# CAN_Bus.net
KiCad netlist of a schematic drawn in Altium Designer
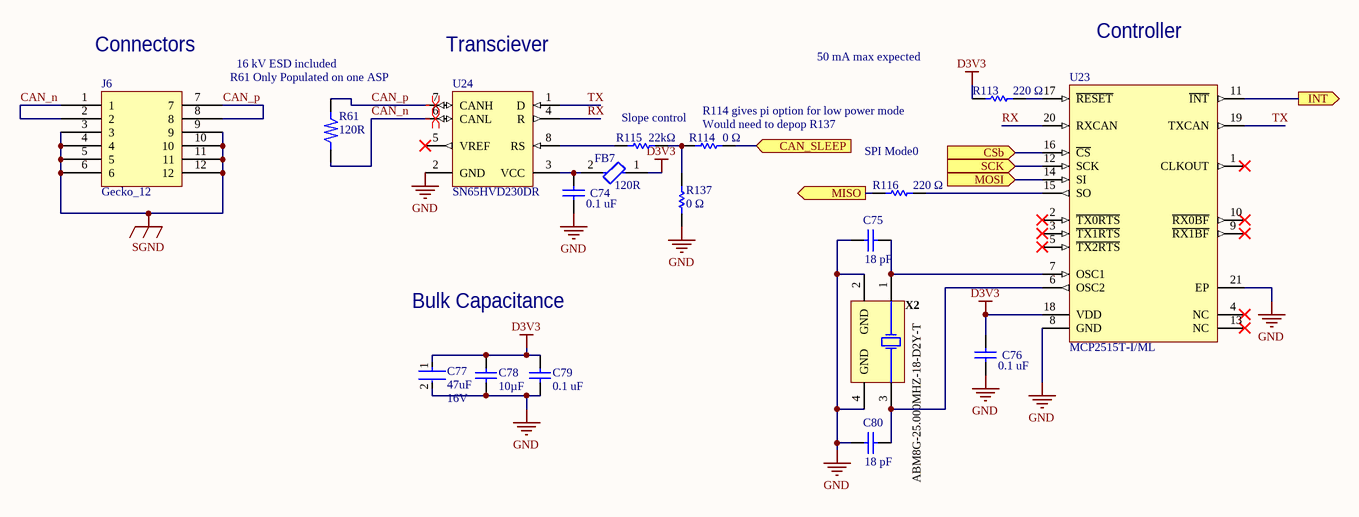
[diagram p0: CAN_Bus.SchDoc]

(export (version "E")
  (design (tool "Eeschema 10.0.6"))
  (components
    (comp (ref "C74")
      (value "0.1 uF")
      (footprint "CAPC0402(1005)60_L")
      (description "CAP 100nF 16V ±5% 0402 (1005 Metric) Thickness 0.6mm SMD")
      (fields (field (name "TOLERANCE") "Â±5%"))
      (libsource (lib "Altium Content Vault") (part "CAP"))
    )
    (comp (ref "C75")
      (value "GRM1555C1H180JA01D")
      (footprint "CAPC1005X55X25LL05T10")
      (fields (field (name "MANUFACTURER") "Murata") (field (name "CAPACITANCE") "18 pF"))
      (libsource (lib "Altium Content Vault") (part "CAP"))
    )
    (comp (ref "C76")
      (value "0.1 uF")
      (footprint "CAPC0402(1005)60_L")
      (description "CAP 100nF 16V ±5% 0402 (1005 Metric) Thickness 0.6mm SMD")
      (fields (field (name "TOLERANCE") "Â±5%"))
      (libsource (lib "Altium Content Vault") (part "CAP"))
    )
    (comp (ref "C77")
      (value "GRT32EC81C476ME13L")
      (footprint "FP-GRT32E-0_3-IPC_C")
      (description "Multi-Layer Ceramic Capacitor 47uF 16V X6S ±20% 1210 Emboss T/R")
      (fields
        (field (name "CAPACITANCE") "47uF")
        (field (name "VOLTAGE RATING") "16V")
        (field (name "TOLERANCE") "20%")
      )
      (libsource (lib "Altium Content Vault") (part "02cd4be3c70576c341d710602a673aa"))
    )
    (comp (ref "C78")
      (value "EMK107BBJ106MA-T")
      (footprint "CAPC1608X100X35LL20T25")
      (description "Chip Capacitor, 10 uF, +/- 20%, 16 V, -55 to 85 degC, 0603 (1608 Metric), RoHS, Tape and Reel")
      (fields
        (field (name "CAPACITANCE") "10µF")
        (field (name "MANUFACTURER") "Taiyo Yuden")
        (field (name "TOLERANCE") "±20%")
      )
      (libsource (lib "Altium Content Vault") (part "CAP-NP-2"))
    )
    (comp (ref "C79")
      (value "0.1 uF")
      (footprint "CAPC0402(1005)60_L")
      (description "CAP 100nF 16V ±5% 0402 (1005 Metric) Thickness 0.6mm SMD")
      (fields (field (name "TOLERANCE") "Â±5%"))
      (libsource (lib "Altium Content Vault") (part "CAP"))
    )
    (comp (ref "C80")
      (value "GRM1555C1H180JA01D")
      (footprint "CAPC1005X55X25LL05T10")
      (fields (field (name "MANUFACTURER") "Murata") (field (name "CAPACITANCE") "18 pF"))
      (libsource (lib "Altium Content Vault") (part "CAP"))
    )
    (comp (ref "FB7")
      (value "BLM18PG121SH1D")
      (footprint "FP-BLM18-0_15-t0_8-IPC_C")
      (description "Chip Ferrite Bead, 0603, 120Ω @ 100MHz, 0.05Ω, 25%, 2A")
      (fields (field (name "IMPEDANCE") "120R") (field (name "TOLERANCE") "25%"))
      (libsource (lib "Altium Content Vault") (part "5f30dd21d616792df468990f7003faa"))
    )
    (comp (ref "J6") (value "Gecko_12") (footprint "GECK12") (libsource (lib "Hrafn") (part "Gecko_12")))
    (comp (ref "R61")
      (value "R")
      (footprint "RESC1608X08L")
      (description "ROHM - ESR03EZPJ121 - RES, AEC-Q200, THICK FILM, 120R, 5%, 0603 ROHS COMPLIANT: YES")
      (fields (field (name "TOLERANCE") "5%") (field (name "RESISTANCE") "120R"))
      (libsource (lib "Hrafn") (part "R"))
    )
    (comp (ref "R113")
      (value "220 Ω")
      (footprint "RESC1005X40X25LL05T05")
      (fields (field (name "PART NUMBER") "CRCW040220K0FKED") (field (name "MANUFACTURER") "Vishay Dale"))
      (libsource (lib "Altium Content Vault") (part "RES"))
    )
    (comp (ref "R114")
      (value "ERJ2GE0R00X")
      (footprint "RESC1005X40X25LL05T05")
      (description "Chip Resistor, 0 Ohm, 0.1 W, -55 to 155 degC, 0402 (1005 Metric), RoHS, Tape and Reel")
      (fields
        (field (name "MANUFACTURER") "Panasonic")
        (field (name "RESISTANCE") "0 Ω")
        (field (name "TOLERANCE") "5%")
      )
      (libsource (lib "Altium Content Vault") (part "RES-2"))
    )
    (comp (ref "R115")
      (value "22kΩ")
      (footprint "RESC1005X40X25LL05T05")
      (fields (field (name "MANUFACTURER") "Panasonic") (field (name "PART NUMBER") "ERJ-2GEJ223X"))
      (libsource (lib "Altium Content Vault") (part "RES"))
    )
    (comp (ref "R116")
      (value "220 Ω")
      (footprint "RESC1005X40X25LL05T05")
      (fields (field (name "PART NUMBER") "CRCW040220K0FKED") (field (name "MANUFACTURER") "Vishay Dale"))
      (libsource (lib "Altium Content Vault") (part "RES"))
    )
    (comp (ref "R137")
      (value "ERJ2GE0R00X")
      (footprint "RESC1005X40X25LL05T05")
      (description "Chip Resistor, 0 Ohm, 0.1 W, -55 to 155 degC, 0402 (1005 Metric), RoHS, Tape and Reel")
      (fields
        (field (name "MANUFACTURER") "Panasonic")
        (field (name "RESISTANCE") "0 Ω")
        (field (name "TOLERANCE") "5%")
      )
      (libsource (lib "Altium Content Vault") (part "RES-2"))
    )
    (comp (ref "U23")
      (value "MCP2515T-I/ML")
      (footprint "QFN-ML20_N")
      (description "Stand-Alone CAN Controller With SPI Interface, 20-Pin QFN, Industrial Temperature, Tape and Reel")
      (libsource (lib "Altium Content Vault") (part "COM-CAN-MCP2515-21"))
    )
    (comp (ref "U24")
      (value "SN65HVD230DR")
      (footprint "D0008A_L")
      (fields (field (name "MANUFACTURER") "Texas Instruments"))
      (libsource (lib "Altium Content Vault") (part "TI-SN65HVD230-SOIC_D-8"))
    )
    (comp (ref "X2")
      (value "ABM8G-25.000MHZ-18-D2Y-T")
      (footprint "ABRA-ABM8G_V")
      (fields (field (name "MANUFACTURER") "ABRACON") (field (name "TOLERANCE") "20PPM"))
      (libsource (lib "Altium Content Vault") (part "XTAL-1-3-4"))
    )
  )
  (nets
    (net (code "1") (name "/CAN_SLEEP") (class "Default")
      (node (ref "R114") (pin "2") (pinfunction "2_2") (pintype "passive"))
    )
    (net (code "2") (name "/CAN_n") (class "Default")
      (node (ref "J6") (pin "1") (pinfunction "1_1") (pintype "passive"))
      (node (ref "J6") (pin "2") (pinfunction "2_2") (pintype "passive"))
      (node (ref "R61") (pin "1") (pinfunction "1_1") (pintype "passive"))
      (node (ref "U24") (pin "6") (pinfunction "CANL_6") (pintype "bidirectional"))
    )
    (net (code "3") (name "/CAN_p") (class "Default")
      (node (ref "J6") (pin "7") (pinfunction "7_7") (pintype "passive"))
      (node (ref "J6") (pin "8") (pinfunction "8_8") (pintype "passive"))
      (node (ref "R61") (pin "0") (pinfunction "0_0") (pintype "passive"))
      (node (ref "U24") (pin "7") (pinfunction "CANH_7") (pintype "bidirectional"))
    )
    (net (code "4") (name "/CSb") (class "Default")
      (node (ref "U23") (pin "16") (pinfunction "~{CS}_16") (pintype "input"))
    )
    (net (code "5") (name "/INT") (class "Default")
      (node (ref "U23") (pin "11") (pinfunction "~{INT}_11") (pintype "output"))
    )
    (net (code "6") (name "/MISO") (class "Default")
      (node (ref "R116") (pin "1") (pinfunction "1_1") (pintype "passive"))
    )
    (net (code "7") (name "/MOSI") (class "Default")
      (node (ref "U23") (pin "14") (pinfunction "SI_14") (pintype "input"))
    )
    (net (code "8") (name "/RX") (class "Default")
      (node (ref "U23") (pin "20") (pinfunction "RXCAN_20") (pintype "input"))
      (node (ref "U24") (pin "4") (pinfunction "R_4") (pintype "output"))
    )
    (net (code "9") (name "/SCK") (class "Default")
      (node (ref "U23") (pin "12") (pinfunction "SCK_12") (pintype "input"))
    )
    (net (code "10") (name "/TX") (class "Default")
      (node (ref "U23") (pin "19") (pinfunction "TXCAN_19") (pintype "output"))
      (node (ref "U24") (pin "1") (pinfunction "D_1") (pintype "input"))
    )
    (net (code "11") (name "D3V3") (class "Default")
      (node (ref "C76") (pin "2") (pinfunction "2_2") (pintype "passive"))
      (node (ref "C77") (pin "1") (pinfunction "1_1") (pintype "passive"))
      (node (ref "C78") (pin "2") (pinfunction "2_2") (pintype "passive"))
      (node (ref "C79") (pin "2") (pinfunction "2_2") (pintype "passive"))
      (node (ref "FB7") (pin "1") (pinfunction "1_1") (pintype "passive"))
      (node (ref "R113") (pin "1") (pinfunction "1_1") (pintype "passive"))
      (node (ref "U23") (pin "18") (pinfunction "VDD_18") (pintype "power_in"))
    )
    (net (code "12") (name "GND") (class "Default")
      (node (ref "C74") (pin "1") (pinfunction "1_1") (pintype "passive"))
      (node (ref "C75") (pin "1") (pinfunction "1_1") (pintype "passive"))
      (node (ref "C76") (pin "1") (pinfunction "1_1") (pintype "passive"))
      (node (ref "C77") (pin "2") (pinfunction "2_2") (pintype "passive"))
      (node (ref "C78") (pin "1") (pinfunction "1_1") (pintype "passive"))
      (node (ref "C79") (pin "1") (pinfunction "1_1") (pintype "passive"))
      (node (ref "C80") (pin "1") (pinfunction "1_1") (pintype "passive"))
      (node (ref "R137") (pin "1") (pinfunction "1_1") (pintype "passive"))
      (node (ref "U23") (pin "21") (pinfunction "EP_21") (pintype "passive"))
      (node (ref "U23") (pin "8") (pinfunction "GND_8") (pintype "power_in"))
      (node (ref "U24") (pin "2") (pinfunction "GND_2") (pintype "power_in"))
      (node (ref "X2") (pin "2") (pinfunction "GND_2") (pintype "power_in"))
      (node (ref "X2") (pin "4") (pinfunction "GND_4") (pintype "power_in"))
    )
    (net (code "13") (name "Net-(R114-Pad1)") (class "Default")
      (node (ref "R114") (pin "1") (pinfunction "1_1") (pintype "passive"))
      (node (ref "R115") (pin "2") (pinfunction "2_2") (pintype "passive"))
      (node (ref "R137") (pin "2") (pinfunction "2_2") (pintype "passive"))
    )
    (net (code "14") (name "Net-(U23-OSC1)") (class "Default")
      (node (ref "C75") (pin "2") (pinfunction "2_2") (pintype "passive"))
      (node (ref "U23") (pin "7") (pinfunction "OSC1_7") (pintype "input"))
      (node (ref "X2") (pin "1") (pinfunction "X1_1") (pintype "passive"))
    )
    (net (code "15") (name "Net-(U23-OSC2)") (class "Default")
      (node (ref "C80") (pin "2") (pinfunction "2_2") (pintype "passive"))
      (node (ref "U23") (pin "6") (pinfunction "OSC2_6") (pintype "output"))
      (node (ref "X2") (pin "3") (pinfunction "X2_3") (pintype "passive"))
    )
    (net (code "16") (name "Net-(U23-SO)") (class "Default")
      (node (ref "R116") (pin "2") (pinfunction "2_2") (pintype "passive"))
      (node (ref "U23") (pin "15") (pinfunction "SO_15") (pintype "output"))
    )
    (net (code "17") (name "Net-(U23-~{RESET})") (class "Default")
      (node (ref "R113") (pin "2") (pinfunction "2_2") (pintype "passive"))
      (node (ref "U23") (pin "17") (pinfunction "~{RESET}_17") (pintype "input"))
    )
    (net (code "18") (name "Net-(U24-RS)") (class "Default")
      (node (ref "R115") (pin "1") (pinfunction "1_1") (pintype "passive"))
      (node (ref "U24") (pin "8") (pinfunction "RS_8") (pintype "input"))
    )
    (net (code "19") (name "Net-(U24-VCC)") (class "Default")
      (node (ref "C74") (pin "2") (pinfunction "2_2") (pintype "passive"))
      (node (ref "FB7") (pin "2") (pinfunction "2_2") (pintype "passive"))
      (node (ref "U24") (pin "3") (pinfunction "VCC_3") (pintype "power_in"))
    )
    (net (code "20") (name "SGND") (class "Default")
      (node (ref "J6") (pin "10") (pinfunction "10_10") (pintype "passive"))
      (node (ref "J6") (pin "11") (pinfunction "11_11") (pintype "passive"))
      (node (ref "J6") (pin "12") (pinfunction "12_12") (pintype "passive"))
      (node (ref "J6") (pin "3") (pinfunction "3_3") (pintype "passive"))
      (node (ref "J6") (pin "4") (pinfunction "4_4") (pintype "passive"))
      (node (ref "J6") (pin "5") (pinfunction "5_5") (pintype "passive"))
      (node (ref "J6") (pin "6") (pinfunction "6_6") (pintype "passive"))
      (node (ref "J6") (pin "9") (pinfunction "9_9") (pintype "passive"))
    )
    (net (code "21") (name "unconnected-(U23-CLKOUT-Pad1)") (class "Default")
      (node (ref "U23") (pin "1") (pinfunction "CLKOUT_1") (pintype "output+no_connect"))
    )
    (net (code "22") (name "unconnected-(U23-NC-Pad4)") (class "Default")
      (node (ref "U23") (pin "4") (pinfunction "NC_4") (pintype "passive+no_connect"))
    )
    (net (code "23") (name "unconnected-(U23-NC-Pad13)") (class "Default")
      (node (ref "U23") (pin "13") (pinfunction "NC_13") (pintype "passive+no_connect"))
    )
    (net (code "24") (name "unconnected-(U23-~{RX0BF}-Pad10)") (class "Default")
      (node (ref "U23") (pin "10") (pinfunction "~{RX0BF}_10") (pintype "output+no_connect"))
    )
    (net (code "25") (name "unconnected-(U23-~{RX1BF}-Pad9)") (class "Default")
      (node (ref "U23") (pin "9") (pinfunction "~{RX1BF}_9") (pintype "output+no_connect"))
    )
    (net (code "26") (name "unconnected-(U23-~{TX0RTS}-Pad2)") (class "Default")
      (node (ref "U23") (pin "2") (pinfunction "~{TX0RTS}_2") (pintype "input+no_connect"))
    )
    (net (code "27") (name "unconnected-(U23-~{TX1RTS}-Pad3)") (class "Default")
      (node (ref "U23") (pin "3") (pinfunction "~{TX1RTS}_3") (pintype "input+no_connect"))
    )
    (net (code "28") (name "unconnected-(U23-~{TX2RTS}-Pad5)") (class "Default")
      (node (ref "U23") (pin "5") (pinfunction "~{TX2RTS}_5") (pintype "input+no_connect"))
    )
    (net (code "29") (name "unconnected-(U24-VREF-Pad5)") (class "Default")
      (node (ref "U24") (pin "5") (pinfunction "VREF_5") (pintype "output+no_connect"))
    )
  )
)
